# RS232toTTL_Rev2.net
KiCad netlist of a schematic drawn in EAGLE
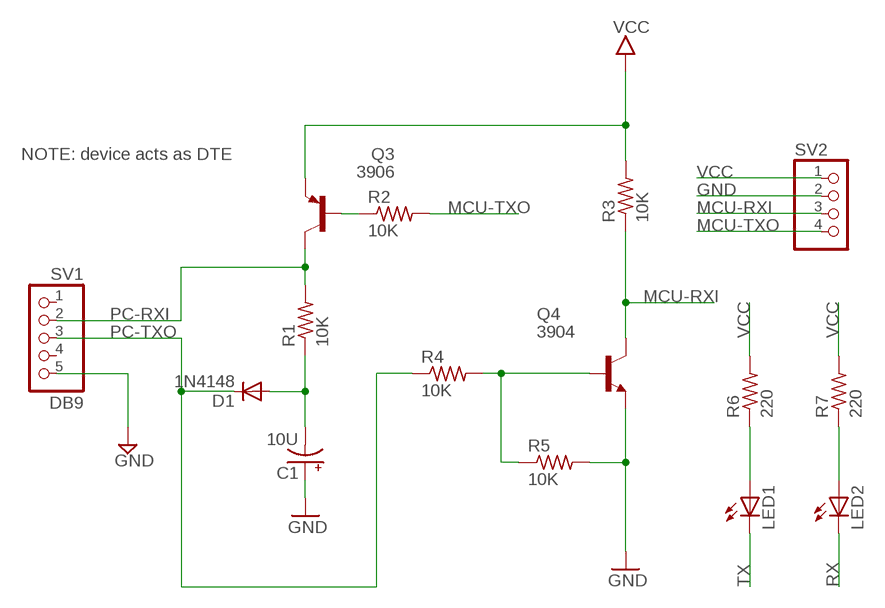
[diagram p0: schematic, sheet 1]

(export (version "E")
  (design (tool "Eeschema 10.0.6"))
  (components
    (comp (ref "C1")
      (value "10U")
      (footprint "eagle-import:E2,5-5")
      (libsource (lib "eagle-import") (part "CPOL-USE2.5-5"))
    )
    (comp (ref "D1")
      (value "1N4148")
      (footprint "eagle-import:DO35-7")
      (libsource (lib "eagle-import") (part "1N4148DO35-7"))
    )
    (comp (ref "LED1")
      (value "LED3MM")
      (footprint "eagle-import:LED3MM")
      (libsource (lib "eagle-import") (part "LED3MM"))
    )
    (comp (ref "LED2")
      (value "LED3MM")
      (footprint "eagle-import:LED3MM")
      (libsource (lib "eagle-import") (part "LED3MM"))
    )
    (comp (ref "Q3")
      (value "3906")
      (footprint "eagle-import:TO92-CBE")
      (libsource (lib "eagle-import") (part "2N3906INLINE"))
    )
    (comp (ref "Q4")
      (value "3904")
      (footprint "eagle-import:TO92-CBE")
      (libsource (lib "eagle-import") (part "2N3904INLINE"))
    )
    (comp (ref "R1")
      (value "10K")
      (footprint "eagle-import:0204_5")
      (libsource (lib "eagle-import") (part "R-US_0204/5"))
    )
    (comp (ref "R2")
      (value "10K")
      (footprint "eagle-import:0204_5")
      (libsource (lib "eagle-import") (part "R-US_0204/5"))
    )
    (comp (ref "R3")
      (value "10K")
      (footprint "eagle-import:0204_5")
      (libsource (lib "eagle-import") (part "R-US_0204/5"))
    )
    (comp (ref "R4")
      (value "10K")
      (footprint "eagle-import:0204_5")
      (libsource (lib "eagle-import") (part "R-US_0204/5"))
    )
    (comp (ref "R5")
      (value "10K")
      (footprint "eagle-import:0204_5")
      (libsource (lib "eagle-import") (part "R-US_0204/5"))
    )
    (comp (ref "R6")
      (value "220")
      (footprint "eagle-import:0204_5")
      (libsource (lib "eagle-import") (part "R-US_0204/5"))
    )
    (comp (ref "R7")
      (value "220")
      (footprint "eagle-import:0204_5")
      (libsource (lib "eagle-import") (part "R-US_0204/5"))
    )
    (comp (ref "SV1")
      (value "DB9")
      (footprint "eagle-import:1X05-S")
      (libsource (lib "eagle-import") (part "PINHD-1X05_2.54-S"))
    )
    (comp (ref "SV2")
      (value "PINHD-1X04_2.54-S")
      (footprint "eagle-import:1X04-S")
      (libsource (lib "eagle-import") (part "PINHD-1X04_2.54-S"))
    )
  )
  (nets
    (net (code "1") (name "/MCU-RXI") (class "Default")
      (node (ref "Q4") (pin "C") (pinfunction "C_C") (pintype "passive"))
      (node (ref "R3") (pin "1") (pinfunction "1_1") (pintype "passive"))
      (node (ref "SV2") (pin "3") (pinfunction "3_3") (pintype "passive"))
    )
    (net (code "2") (name "/MCU-TXO") (class "Default")
      (node (ref "R2") (pin "2") (pinfunction "2_2") (pintype "passive"))
      (node (ref "SV2") (pin "4") (pinfunction "4_4") (pintype "passive"))
    )
    (net (code "3") (name "/PC-RXI") (class "Default")
      (node (ref "Q3") (pin "C") (pinfunction "C_C") (pintype "passive"))
      (node (ref "R1") (pin "2") (pinfunction "2_2") (pintype "passive"))
      (node (ref "SV1") (pin "2") (pinfunction "2_2") (pintype "passive"))
    )
    (net (code "4") (name "/PC-TXO") (class "Default")
      (node (ref "D1") (pin "C") (pinfunction "C_C") (pintype "passive"))
      (node (ref "R4") (pin "1") (pinfunction "1_1") (pintype "passive"))
      (node (ref "SV1") (pin "3") (pinfunction "3_3") (pintype "passive"))
    )
    (net (code "5") (name "/RX") (class "Default")
      (node (ref "LED2") (pin "K") (pinfunction "C_K") (pintype "passive"))
    )
    (net (code "6") (name "/TX") (class "Default")
      (node (ref "LED1") (pin "K") (pinfunction "C_K") (pintype "passive"))
    )
    (net (code "7") (name "GND") (class "Default")
      (node (ref "C1") (pin "+") (pinfunction "+_+") (pintype "passive"))
      (node (ref "Q4") (pin "E") (pinfunction "E_E") (pintype "passive"))
      (node (ref "R5") (pin "2") (pinfunction "2_2") (pintype "passive"))
      (node (ref "SV1") (pin "5") (pinfunction "5_5") (pintype "passive"))
      (node (ref "SV2") (pin "2") (pinfunction "2_2") (pintype "passive"))
    )
    (net (code "8") (name "Net-(C1-Pad-)") (class "Default")
      (node (ref "C1") (pin "-") (pinfunction "-_-") (pintype "passive"))
      (node (ref "D1") (pin "A") (pinfunction "A_A") (pintype "passive"))
      (node (ref "R1") (pin "1") (pinfunction "1_1") (pintype "passive"))
    )
    (net (code "9") (name "Net-(LED1-PadA)") (class "Default")
      (node (ref "LED1") (pin "A") (pinfunction "A_A") (pintype "passive"))
      (node (ref "R6") (pin "1") (pinfunction "1_1") (pintype "passive"))
    )
    (net (code "10") (name "Net-(LED2-PadA)") (class "Default")
      (node (ref "LED2") (pin "A") (pinfunction "A_A") (pintype "passive"))
      (node (ref "R7") (pin "1") (pinfunction "1_1") (pintype "passive"))
    )
    (net (code "11") (name "Net-(Q3-PadB)") (class "Default")
      (node (ref "Q3") (pin "B") (pinfunction "B_B") (pintype "passive"))
      (node (ref "R2") (pin "1") (pinfunction "1_1") (pintype "passive"))
    )
    (net (code "12") (name "Net-(Q4-PadB)") (class "Default")
      (node (ref "Q4") (pin "B") (pinfunction "B_B") (pintype "passive"))
      (node (ref "R4") (pin "2") (pinfunction "2_2") (pintype "passive"))
      (node (ref "R5") (pin "1") (pinfunction "1_1") (pintype "passive"))
    )
    (net (code "13") (name "VCC") (class "Default")
      (node (ref "Q3") (pin "E") (pinfunction "E_E") (pintype "passive"))
      (node (ref "R3") (pin "2") (pinfunction "2_2") (pintype "passive"))
      (node (ref "R6") (pin "2") (pinfunction "2_2") (pintype "passive"))
      (node (ref "R7") (pin "2") (pinfunction "2_2") (pintype "passive"))
      (node (ref "SV2") (pin "1") (pinfunction "1_1") (pintype "passive"))
    )
    (net (code "14") (name "unconnected-(SV1-Pad1)") (class "Default")
      (node (ref "SV1") (pin "1") (pinfunction "1_1") (pintype "passive"))
    )
    (net (code "15") (name "unconnected-(SV1-Pad4)") (class "Default")
      (node (ref "SV1") (pin "4") (pinfunction "4_4") (pintype "passive"))
    )
  )
)
